# Sheet1.net
KiCad netlist of a schematic drawn in Altium Designer
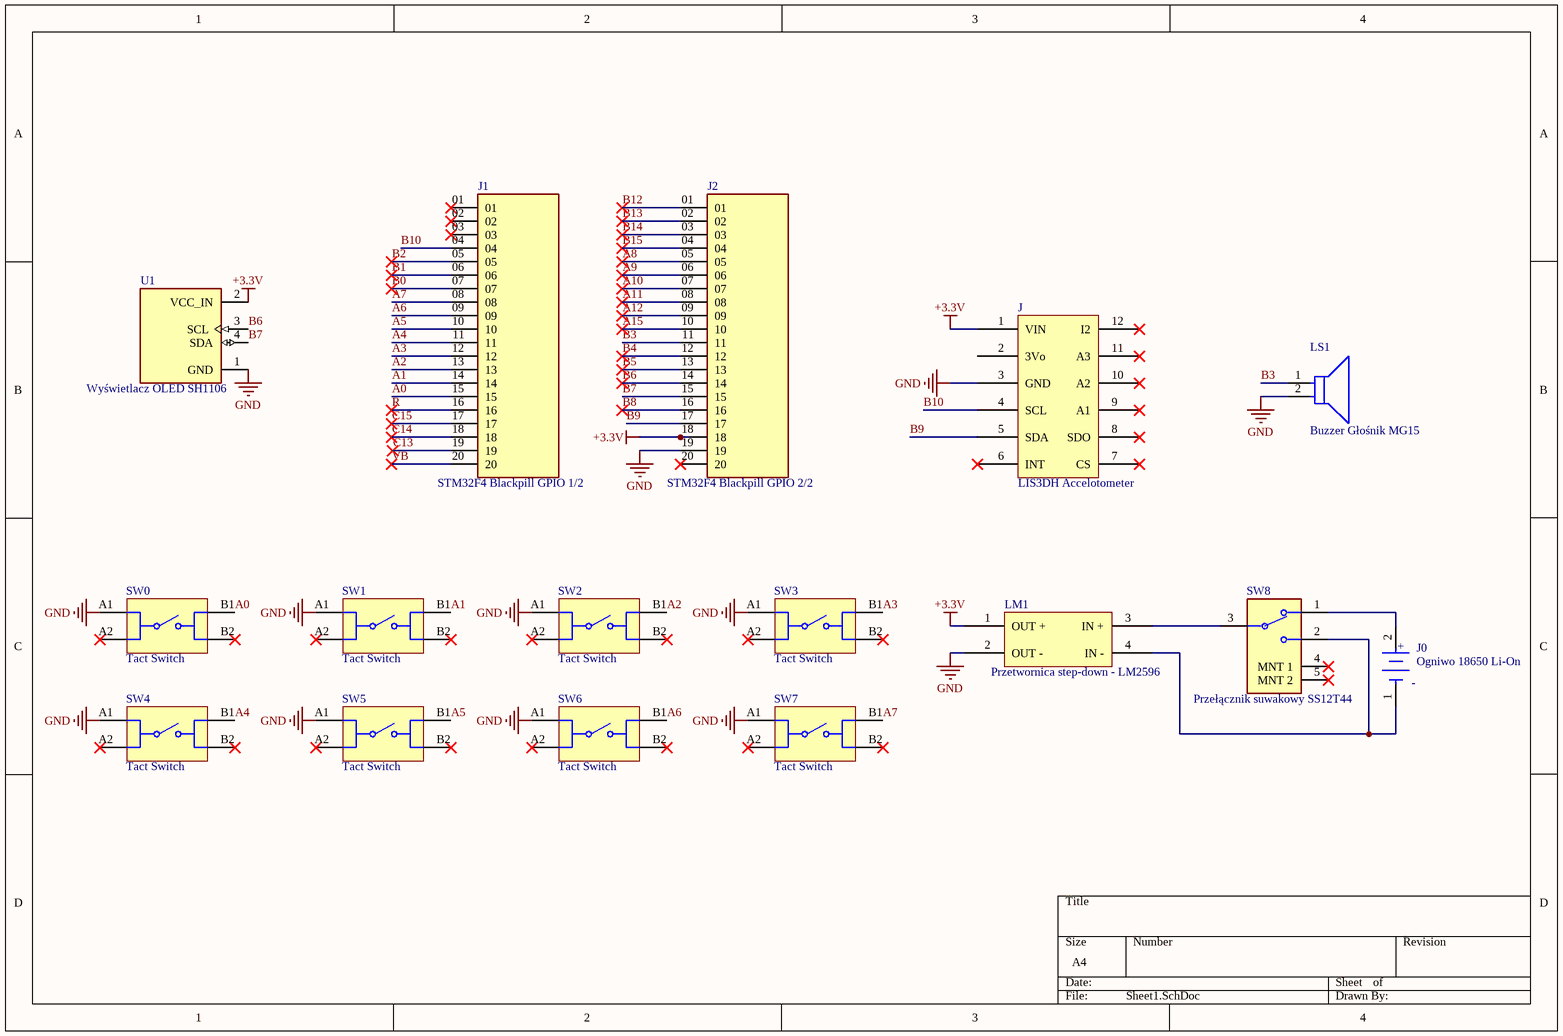
[diagram p0: Sheet1.SchDoc]

(export (version "E")
  (design (tool "Eeschema 10.0.6"))
  (components
    (comp (ref "J")
      (value "LIS3DH Accelotometer")
      (footprint "LIS3DH:PCBComponent_1")
      (libsource (lib "2809 LIS3DH") (part "LIS3DH"))
    )
    (comp (ref "J0")
      (value "Ogniwo 18650 Li-On")
      (footprint "FP-1043P-MFG")
      (description "BATT HOLDER 18650 1 CELL PC PIN")
      (libsource (lib "Altium Content Vault") (part "60d3b5b901a8747834971d0eb8cf3fd"))
    )
    (comp (ref "J1")
      (value "STM32F4 Blackpill GPIO 1/2")
      (footprint "SAMTEC_TS-120-T-AA")
      (description "Headers & Wire Housings .100 Single Row Screw Machine Terminal Strip")
      (fields (field (name "MF") "Samtec") (field (name "MP") "TS-120-T-AA"))
      (libsource (lib "TS-120-T-AA") (part "TS-120-T-AA"))
    )
    (comp (ref "J2")
      (value "STM32F4 Blackpill GPIO 2/2")
      (footprint "SAMTEC_TS-120-T-AA")
      (description "Headers & Wire Housings .100 Single Row Screw Machine Terminal Strip")
      (fields (field (name "MF") "Samtec") (field (name "MP") "TS-120-T-AA"))
      (libsource (lib "TS-120-T-AA") (part "TS-120-T-AA"))
    )
    (comp (ref "LM1")
      (value "Przetwornica step-down - LM2596")
      (footprint "LM2596:PCBComponent_1")
      (libsource (lib "LM2596") (part "LM2596"))
    )
    (comp (ref "LS1")
      (value "Buzzer Głośnik MG15")
      (footprint "FP-SDC1610MT-01-MFG")
      (description "AUDIO MAGNETIC IND 8-16V TH")
      (libsource (lib "Altium Content Vault") (part "1973c4b650225fd2ddacaff6b763965"))
    )
    (comp (ref "SW0")
      (value "Tact Switch")
      (footprint "430476043716")
      (description "Switch Tactile Spst-no 0.05A 12V")
      (libsource (lib "Altium Content Vault") (part "SPST-NO_4P"))
    )
    (comp (ref "SW1")
      (value "Tact Switch")
      (footprint "430476043716")
      (description "Switch Tactile Spst-no 0.05A 12V")
      (libsource (lib "Altium Content Vault") (part "SPST-NO_4P"))
    )
    (comp (ref "SW2")
      (value "Tact Switch")
      (footprint "430476043716")
      (description "Switch Tactile Spst-no 0.05A 12V")
      (libsource (lib "Altium Content Vault") (part "SPST-NO_4P"))
    )
    (comp (ref "SW3")
      (value "Tact Switch")
      (footprint "430476043716")
      (description "Switch Tactile Spst-no 0.05A 12V")
      (libsource (lib "Altium Content Vault") (part "SPST-NO_4P"))
    )
    (comp (ref "SW4")
      (value "Tact Switch")
      (footprint "430476043716")
      (description "Switch Tactile Spst-no 0.05A 12V")
      (libsource (lib "Altium Content Vault") (part "SPST-NO_4P"))
    )
    (comp (ref "SW5")
      (value "Tact Switch")
      (footprint "430476043716")
      (description "Switch Tactile Spst-no 0.05A 12V")
      (libsource (lib "Altium Content Vault") (part "SPST-NO_4P"))
    )
    (comp (ref "SW6")
      (value "Tact Switch")
      (footprint "430476043716")
      (description "Switch Tactile Spst-no 0.05A 12V")
      (libsource (lib "Altium Content Vault") (part "SPST-NO_4P"))
    )
    (comp (ref "SW7")
      (value "Tact Switch")
      (footprint "430476043716")
      (description "Switch Tactile Spst-no 0.05A 12V")
      (libsource (lib "Altium Content Vault") (part "SPST-NO_4P"))
    )
    (comp (ref "SW8")
      (value "Przełącznik suwakowy SS12T44")
      (footprint "FP-CSS-1210TB-MFG")
      (description "SWITCH SLIDE SPDT 100MA 12V")
      (libsource (lib "Altium Content Vault") (part "235c6d1c3a5894744d06c60f0199c3d"))
    )
    (comp (ref "U1")
      (value "Wyświetlacz OLED SH1106")
      (footprint "MODULE_DM-OLED096-636")
      (description "0.96â€ 128 X 64 MONOCHROME GRAPHIC OLED DISPLAY MODULE - I2C")
      (fields (field (name "MF") "Display Module") (field (name "MP") "DM-OLED096-636"))
      (libsource (lib "DM-OLED096-636") (part "DM-OLED096-636"))
    )
  )
  (nets
    (net (code "1") (name "+3.3V") (class "Default")
      (node (ref "J") (pin "1") (pinfunction "VIN_1") (pintype "passive"))
      (node (ref "J2") (pin "18") (pinfunction "18_18") (pintype "passive"))
      (node (ref "LM1") (pin "1") (pinfunction "OUT_+_1") (pintype "passive"))
      (node (ref "U1") (pin "2") (pinfunction "VCC_IN_2") (pintype "power_in"))
    )
    (net (code "2") (name "/A0") (class "Default")
      (node (ref "J1") (pin "15") (pinfunction "15_15") (pintype "passive"))
      (node (ref "SW0") (pin "B1") (pinfunction "B1_B1") (pintype "passive"))
    )
    (net (code "3") (name "/A1") (class "Default")
      (node (ref "J1") (pin "14") (pinfunction "14_14") (pintype "passive"))
      (node (ref "SW1") (pin "B1") (pinfunction "B1_B1") (pintype "passive"))
    )
    (net (code "4") (name "/A2") (class "Default")
      (node (ref "J1") (pin "13") (pinfunction "13_13") (pintype "passive"))
      (node (ref "SW2") (pin "B1") (pinfunction "B1_B1") (pintype "passive"))
    )
    (net (code "5") (name "/A3") (class "Default")
      (node (ref "J1") (pin "12") (pinfunction "12_12") (pintype "passive"))
      (node (ref "SW3") (pin "B1") (pinfunction "B1_B1") (pintype "passive"))
    )
    (net (code "6") (name "/A4") (class "Default")
      (node (ref "J1") (pin "11") (pinfunction "11_11") (pintype "passive"))
      (node (ref "SW4") (pin "B1") (pinfunction "B1_B1") (pintype "passive"))
    )
    (net (code "7") (name "/A5") (class "Default")
      (node (ref "J1") (pin "10") (pinfunction "10_10") (pintype "passive"))
      (node (ref "SW5") (pin "B1") (pinfunction "B1_B1") (pintype "passive"))
    )
    (net (code "8") (name "/A6") (class "Default")
      (node (ref "J1") (pin "09") (pinfunction "09_09") (pintype "passive"))
      (node (ref "SW6") (pin "B1") (pinfunction "B1_B1") (pintype "passive"))
    )
    (net (code "9") (name "/A7") (class "Default")
      (node (ref "J1") (pin "08") (pinfunction "08_08") (pintype "passive"))
      (node (ref "SW7") (pin "B1") (pinfunction "B1_B1") (pintype "passive"))
    )
    (net (code "10") (name "/A8") (class "Default")
      (node (ref "J2") (pin "05") (pinfunction "05_05") (pintype "passive+no_connect"))
    )
    (net (code "11") (name "/A9") (class "Default")
      (node (ref "J2") (pin "06") (pinfunction "06_06") (pintype "passive+no_connect"))
    )
    (net (code "12") (name "/A10") (class "Default")
      (node (ref "J2") (pin "07") (pinfunction "07_07") (pintype "passive+no_connect"))
    )
    (net (code "13") (name "/A11") (class "Default")
      (node (ref "J2") (pin "08") (pinfunction "08_08") (pintype "passive+no_connect"))
    )
    (net (code "14") (name "/A12") (class "Default")
      (node (ref "J2") (pin "09") (pinfunction "09_09") (pintype "passive+no_connect"))
    )
    (net (code "15") (name "/A15") (class "Default")
      (node (ref "J2") (pin "10") (pinfunction "10_10") (pintype "passive+no_connect"))
    )
    (net (code "16") (name "/B0") (class "Default")
      (node (ref "J1") (pin "07") (pinfunction "07_07") (pintype "passive+no_connect"))
    )
    (net (code "17") (name "/B1") (class "Default")
      (node (ref "J1") (pin "06") (pinfunction "06_06") (pintype "passive+no_connect"))
    )
    (net (code "18") (name "/B2") (class "Default")
      (node (ref "J1") (pin "05") (pinfunction "05_05") (pintype "passive+no_connect"))
    )
    (net (code "19") (name "/B3") (class "Default")
      (node (ref "J2") (pin "11") (pinfunction "11_11") (pintype "passive"))
      (node (ref "LS1") (pin "1") (pinfunction "C_1") (pintype "passive"))
    )
    (net (code "20") (name "/B4") (class "Default")
      (node (ref "J2") (pin "12") (pinfunction "12_12") (pintype "passive+no_connect"))
    )
    (net (code "21") (name "/B5") (class "Default")
      (node (ref "J2") (pin "13") (pinfunction "13_13") (pintype "passive+no_connect"))
    )
    (net (code "22") (name "/B6") (class "Default")
      (node (ref "J2") (pin "14") (pinfunction "14_14") (pintype "passive"))
      (node (ref "U1") (pin "3") (pinfunction "SCL_3") (pintype "input"))
    )
    (net (code "23") (name "/B7") (class "Default")
      (node (ref "J2") (pin "15") (pinfunction "15_15") (pintype "passive"))
      (node (ref "U1") (pin "4") (pinfunction "SDA_4") (pintype "bidirectional"))
    )
    (net (code "24") (name "/B8") (class "Default")
      (node (ref "J2") (pin "16") (pinfunction "16_16") (pintype "passive+no_connect"))
    )
    (net (code "25") (name "/B9") (class "Default")
      (node (ref "J") (pin "5") (pinfunction "SDA_5") (pintype "passive"))
      (node (ref "J2") (pin "17") (pinfunction "17_17") (pintype "passive"))
    )
    (net (code "26") (name "/B10") (class "Default")
      (node (ref "J") (pin "4") (pinfunction "SCL_4") (pintype "passive"))
      (node (ref "J1") (pin "04") (pinfunction "04_04") (pintype "passive"))
    )
    (net (code "27") (name "/B12") (class "Default")
      (node (ref "J2") (pin "01") (pinfunction "01_01") (pintype "passive+no_connect"))
    )
    (net (code "28") (name "/B13") (class "Default")
      (node (ref "J2") (pin "02") (pinfunction "02_02") (pintype "passive+no_connect"))
    )
    (net (code "29") (name "/B14") (class "Default")
      (node (ref "J2") (pin "03") (pinfunction "03_03") (pintype "passive+no_connect"))
    )
    (net (code "30") (name "/B15") (class "Default")
      (node (ref "J2") (pin "04") (pinfunction "04_04") (pintype "passive+no_connect"))
    )
    (net (code "31") (name "/C13") (class "Default")
      (node (ref "J1") (pin "19") (pinfunction "19_19") (pintype "passive+no_connect"))
    )
    (net (code "32") (name "/C14") (class "Default")
      (node (ref "J1") (pin "18") (pinfunction "18_18") (pintype "passive+no_connect"))
    )
    (net (code "33") (name "/C15") (class "Default")
      (node (ref "J1") (pin "17") (pinfunction "17_17") (pintype "passive+no_connect"))
    )
    (net (code "34") (name "/R") (class "Default")
      (node (ref "J1") (pin "16") (pinfunction "16_16") (pintype "passive+no_connect"))
    )
    (net (code "35") (name "/VB") (class "Default")
      (node (ref "J1") (pin "20") (pinfunction "20_20") (pintype "passive+no_connect"))
    )
    (net (code "36") (name "GND") (class "Default")
      (node (ref "J") (pin "3") (pinfunction "GND_3") (pintype "passive"))
      (node (ref "J2") (pin "19") (pinfunction "19_19") (pintype "passive"))
      (node (ref "LM1") (pin "2") (pinfunction "OUT_-_2") (pintype "passive"))
      (node (ref "LS1") (pin "2") (pinfunction "A_2") (pintype "passive"))
      (node (ref "SW0") (pin "A1") (pinfunction "A1_A1") (pintype "passive"))
      (node (ref "SW1") (pin "A1") (pinfunction "A1_A1") (pintype "passive"))
      (node (ref "SW2") (pin "A1") (pinfunction "A1_A1") (pintype "passive"))
      (node (ref "SW3") (pin "A1") (pinfunction "A1_A1") (pintype "passive"))
      (node (ref "SW4") (pin "A1") (pinfunction "A1_A1") (pintype "passive"))
      (node (ref "SW5") (pin "A1") (pinfunction "A1_A1") (pintype "passive"))
      (node (ref "SW6") (pin "A1") (pinfunction "A1_A1") (pintype "passive"))
      (node (ref "SW7") (pin "A1") (pinfunction "A1_A1") (pintype "passive"))
      (node (ref "U1") (pin "1") (pinfunction "GND_1") (pintype "power_in"))
    )
    (net (code "37") (name "Net-(J0-A)") (class "Default")
      (node (ref "J0") (pin "2") (pinfunction "A_2") (pintype "passive"))
      (node (ref "SW8") (pin "1") (pinfunction "1_1") (pintype "passive"))
    )
    (net (code "38") (name "Net-(J0-C)") (class "Default")
      (node (ref "J0") (pin "1") (pinfunction "C_1") (pintype "passive"))
      (node (ref "LM1") (pin "4") (pinfunction "IN_-_4") (pintype "passive"))
      (node (ref "SW8") (pin "2") (pinfunction "2_2") (pintype "passive"))
    )
    (net (code "39") (name "Net-(LM1-IN_+)") (class "Default")
      (node (ref "LM1") (pin "3") (pinfunction "IN_+_3") (pintype "passive"))
      (node (ref "SW8") (pin "3") (pinfunction "C_3") (pintype "passive"))
    )
    (net (code "40") (name "unconnected-(J-3Vo-Pad2)") (class "Default")
      (node (ref "J") (pin "2") (pinfunction "3Vo_2") (pintype "passive"))
    )
    (net (code "41") (name "unconnected-(J-A1-Pad9)") (class "Default")
      (node (ref "J") (pin "9") (pinfunction "A1_9") (pintype "passive+no_connect"))
    )
    (net (code "42") (name "unconnected-(J-A2-Pad10)") (class "Default")
      (node (ref "J") (pin "10") (pinfunction "A2_10") (pintype "passive+no_connect"))
    )
    (net (code "43") (name "unconnected-(J-A3-Pad11)") (class "Default")
      (node (ref "J") (pin "11") (pinfunction "A3_11") (pintype "passive+no_connect"))
    )
    (net (code "44") (name "unconnected-(J-CS-Pad7)") (class "Default")
      (node (ref "J") (pin "7") (pinfunction "CS_7") (pintype "passive+no_connect"))
    )
    (net (code "45") (name "unconnected-(J-I2-Pad12)") (class "Default")
      (node (ref "J") (pin "12") (pinfunction "I2_12") (pintype "passive+no_connect"))
    )
    (net (code "46") (name "unconnected-(J-INT-Pad6)") (class "Default")
      (node (ref "J") (pin "6") (pinfunction "INT_6") (pintype "passive+no_connect"))
    )
    (net (code "47") (name "unconnected-(J-SDO-Pad8)") (class "Default")
      (node (ref "J") (pin "8") (pinfunction "SDO_8") (pintype "passive+no_connect"))
    )
    (net (code "48") (name "unconnected-(J1-Pad01)") (class "Default")
      (node (ref "J1") (pin "01") (pinfunction "01_01") (pintype "passive+no_connect"))
    )
    (net (code "49") (name "unconnected-(J1-Pad02)") (class "Default")
      (node (ref "J1") (pin "02") (pinfunction "02_02") (pintype "passive+no_connect"))
    )
    (net (code "50") (name "unconnected-(J1-Pad03)") (class "Default")
      (node (ref "J1") (pin "03") (pinfunction "03_03") (pintype "passive+no_connect"))
    )
    (net (code "51") (name "unconnected-(J2-Pad20)") (class "Default")
      (node (ref "J2") (pin "20") (pinfunction "20_20") (pintype "passive+no_connect"))
    )
    (net (code "52") (name "unconnected-(SW0-PadA2)") (class "Default")
      (node (ref "SW0") (pin "A2") (pinfunction "A2_A2") (pintype "passive+no_connect"))
    )
    (net (code "53") (name "unconnected-(SW0-PadB2)") (class "Default")
      (node (ref "SW0") (pin "B2") (pinfunction "B2_B2") (pintype "passive+no_connect"))
    )
    (net (code "54") (name "unconnected-(SW1-PadA2)") (class "Default")
      (node (ref "SW1") (pin "A2") (pinfunction "A2_A2") (pintype "passive+no_connect"))
    )
    (net (code "55") (name "unconnected-(SW1-PadB2)") (class "Default")
      (node (ref "SW1") (pin "B2") (pinfunction "B2_B2") (pintype "passive+no_connect"))
    )
    (net (code "56") (name "unconnected-(SW2-PadA2)") (class "Default")
      (node (ref "SW2") (pin "A2") (pinfunction "A2_A2") (pintype "passive+no_connect"))
    )
    (net (code "57") (name "unconnected-(SW2-PadB2)") (class "Default")
      (node (ref "SW2") (pin "B2") (pinfunction "B2_B2") (pintype "passive+no_connect"))
    )
    (net (code "58") (name "unconnected-(SW3-PadA2)") (class "Default")
      (node (ref "SW3") (pin "A2") (pinfunction "A2_A2") (pintype "passive+no_connect"))
    )
    (net (code "59") (name "unconnected-(SW3-PadB2)") (class "Default")
      (node (ref "SW3") (pin "B2") (pinfunction "B2_B2") (pintype "passive+no_connect"))
    )
    (net (code "60") (name "unconnected-(SW4-PadA2)") (class "Default")
      (node (ref "SW4") (pin "A2") (pinfunction "A2_A2") (pintype "passive+no_connect"))
    )
    (net (code "61") (name "unconnected-(SW4-PadB2)") (class "Default")
      (node (ref "SW4") (pin "B2") (pinfunction "B2_B2") (pintype "passive+no_connect"))
    )
    (net (code "62") (name "unconnected-(SW5-PadA2)") (class "Default")
      (node (ref "SW5") (pin "A2") (pinfunction "A2_A2") (pintype "passive+no_connect"))
    )
    (net (code "63") (name "unconnected-(SW5-PadB2)") (class "Default")
      (node (ref "SW5") (pin "B2") (pinfunction "B2_B2") (pintype "passive+no_connect"))
    )
    (net (code "64") (name "unconnected-(SW6-PadA2)") (class "Default")
      (node (ref "SW6") (pin "A2") (pinfunction "A2_A2") (pintype "passive+no_connect"))
    )
    (net (code "65") (name "unconnected-(SW6-PadB2)") (class "Default")
      (node (ref "SW6") (pin "B2") (pinfunction "B2_B2") (pintype "passive+no_connect"))
    )
    (net (code "66") (name "unconnected-(SW7-PadA2)") (class "Default")
      (node (ref "SW7") (pin "A2") (pinfunction "A2_A2") (pintype "passive+no_connect"))
    )
    (net (code "67") (name "unconnected-(SW7-PadB2)") (class "Default")
      (node (ref "SW7") (pin "B2") (pinfunction "B2_B2") (pintype "passive+no_connect"))
    )
    (net (code "68") (name "unconnected-(SW8-MNT_1-Pad4)") (class "Default")
      (node (ref "SW8") (pin "4") (pinfunction "MNT_1_4") (pintype "passive+no_connect"))
    )
    (net (code "69") (name "unconnected-(SW8-MNT_2-Pad5)") (class "Default")
      (node (ref "SW8") (pin "5") (pinfunction "MNT_2_5") (pintype "passive+no_connect"))
    )
  )
)
